# rat_redraw.net
KiCad netlist of a schematic drawn in EAGLE
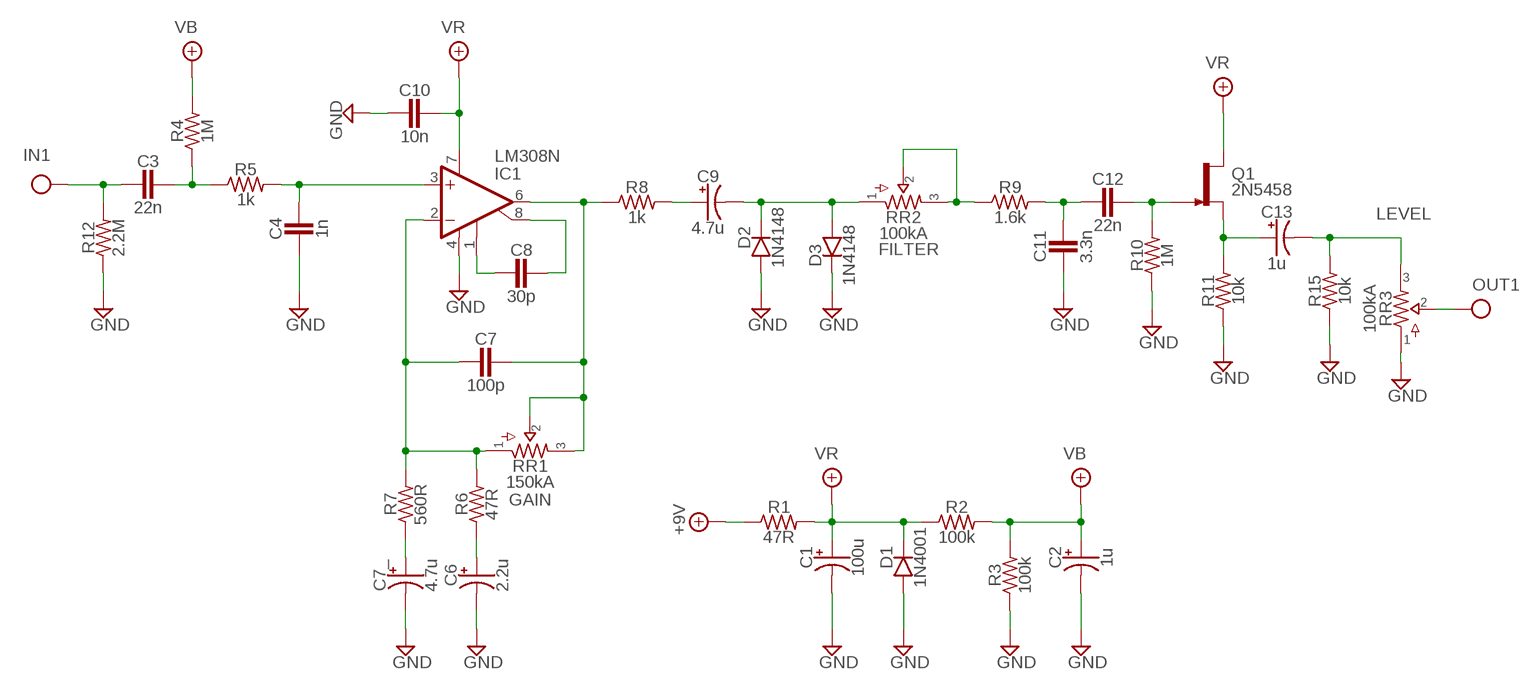
[diagram p0: schematic, sheet 1]

(export (version "E")
  (design (tool "Eeschema 10.0.6"))
  (components
    (comp (ref "C1")
      (value "100u")
      (footprint "eagle-import:040_020")
      (libsource (lib "eagle-import") (part "0400"))
    )
    (comp (ref "C2")
      (value "1u")
      (footprint "eagle-import:040_020")
      (libsource (lib "eagle-import") (part "0400"))
    )
    (comp (ref "C3")
      (value "22n")
      (footprint "eagle-import:BOX_SMALL")
      (libsource (lib "eagle-import") (part "CER/FILMBOX.1"))
    )
    (comp (ref "C4")
      (value "1n")
      (footprint "eagle-import:BOX_SMALL")
      (libsource (lib "eagle-import") (part "CER/FILMBOX.1"))
    )
    (comp (ref "C6")
      (value "2.2u")
      (footprint "eagle-import:050_020")
      (libsource (lib "eagle-import") (part "0500"))
    )
    (comp (ref "C7")
      (value "100p")
      (footprint "eagle-import:050X030_025_2")
      (libsource (lib "eagle-import") (part "CER/FILM2"))
    )
    (comp (ref "C7_")
      (value "4.7u")
      (footprint "eagle-import:050_020")
      (libsource (lib "eagle-import") (part "0500"))
    )
    (comp (ref "C8")
      (value "30p")
      (footprint "eagle-import:050X030_025_2")
      (libsource (lib "eagle-import") (part "CER/FILM2"))
    )
    (comp (ref "C9")
      (value "4.7u")
      (footprint "eagle-import:050_020")
      (libsource (lib "eagle-import") (part "0500"))
    )
    (comp (ref "C10")
      (value "10n")
      (footprint "eagle-import:050X030_025_2")
      (libsource (lib "eagle-import") (part "CER/FILM2"))
    )
    (comp (ref "C11")
      (value "3.3n")
      (footprint "eagle-import:BOX_SMALL")
      (libsource (lib "eagle-import") (part "CER/FILMBOX.1"))
    )
    (comp (ref "C12")
      (value "22n")
      (footprint "eagle-import:BOX_SMALL")
      (libsource (lib "eagle-import") (part "CER/FILMBOX.1"))
    )
    (comp (ref "C13")
      (value "1u")
      (footprint "eagle-import:050_020")
      (libsource (lib "eagle-import") (part "0500"))
    )
    (comp (ref "D1")
      (value "1N4001")
      (footprint "eagle-import:DO35-2")
      (libsource (lib "eagle-import") (part "DO35.2"))
    )
    (comp (ref "D2")
      (value "1N4148")
      (footprint "eagle-import:DO35-2")
      (libsource (lib "eagle-import") (part "DO35.2"))
    )
    (comp (ref "D3")
      (value "1N4148")
      (footprint "eagle-import:DO35-2")
      (libsource (lib "eagle-import") (part "DO35.2"))
    )
    (comp (ref "IC1")
      (value "LM308N")
      (footprint "eagle-import:DIL0")
      (libsource (lib "eagle-import") (part "LM308N"))
    )
    (comp (ref "Q1")
      (value "2N5458")
      (footprint "eagle-import:TO92-")
      (libsource (lib "eagle-import") (part "2N5457"))
    )
    (comp (ref "R1")
      (value "47R")
      (footprint "eagle-import:R0207_3")
      (libsource (lib "eagle-import") (part "R_.3B"))
    )
    (comp (ref "R2")
      (value "100k")
      (footprint "eagle-import:R0207_3")
      (libsource (lib "eagle-import") (part "R_.3B"))
    )
    (comp (ref "R3")
      (value "100k")
      (footprint "eagle-import:R0207_3")
      (libsource (lib "eagle-import") (part "R_.3B"))
    )
    (comp (ref "R4")
      (value "1M")
      (footprint "eagle-import:R0207_3")
      (libsource (lib "eagle-import") (part "R_.3B"))
    )
    (comp (ref "R5")
      (value "1k")
      (footprint "eagle-import:R0207_3")
      (libsource (lib "eagle-import") (part "R_.3B"))
    )
    (comp (ref "R6")
      (value "47R")
      (footprint "eagle-import:R0207_3")
      (libsource (lib "eagle-import") (part "R_.3B"))
    )
    (comp (ref "R7")
      (value "560R")
      (footprint "eagle-import:R0207_3")
      (libsource (lib "eagle-import") (part "R_.3B"))
    )
    (comp (ref "R8")
      (value "1k")
      (footprint "eagle-import:R0207_3")
      (libsource (lib "eagle-import") (part "R_.3B"))
    )
    (comp (ref "R9")
      (value "1.6k")
      (footprint "eagle-import:R0207_3")
      (libsource (lib "eagle-import") (part "R_.3B"))
    )
    (comp (ref "R10")
      (value "1M")
      (footprint "eagle-import:R0207_3")
      (libsource (lib "eagle-import") (part "R_.3B"))
    )
    (comp (ref "R11")
      (value "10k")
      (footprint "eagle-import:R0207_3")
      (libsource (lib "eagle-import") (part "R_.3B"))
    )
    (comp (ref "R12")
      (value "2.2M")
      (footprint "eagle-import:R0207_3")
      (libsource (lib "eagle-import") (part "R_.3B"))
    )
    (comp (ref "R15")
      (value "10k")
      (footprint "eagle-import:R0207_3")
      (libsource (lib "eagle-import") (part "R_.3B"))
    )
    (comp (ref "RR1")
      (value "150kA")
      (footprint "eagle-import:16MM")
      (libsource (lib "eagle-import") (part "POTS16MM"))
    )
    (comp (ref "RR2")
      (value "100kA")
      (footprint "eagle-import:16MM")
      (libsource (lib "eagle-import") (part "POTS16MM"))
    )
    (comp (ref "RR3")
      (value "100kA")
      (footprint "eagle-import:16MM")
      (libsource (lib "eagle-import") (part "POTS16MM"))
    )
  )
  (nets
    (net (code "1") (name "+9V") (class "Default")
      (node (ref "R1") (pin "1") (pinfunction "1_1") (pintype "passive"))
    )
    (net (code "2") (name "GND") (class "Default")
      (node (ref "C1") (pin "-") (pinfunction "-_-") (pintype "passive"))
      (node (ref "C10") (pin "2") (pinfunction "2_2") (pintype "passive"))
      (node (ref "C11") (pin "2") (pinfunction "2_2") (pintype "passive"))
      (node (ref "C2") (pin "-") (pinfunction "-_-") (pintype "passive"))
      (node (ref "C4") (pin "2") (pinfunction "2_2") (pintype "passive"))
      (node (ref "C6") (pin "-") (pinfunction "-_-") (pintype "passive"))
      (node (ref "C7_") (pin "-") (pinfunction "-_-") (pintype "passive"))
      (node (ref "D1") (pin "A") (pinfunction "A_A") (pintype "passive"))
      (node (ref "D2") (pin "A") (pinfunction "A_A") (pintype "passive"))
      (node (ref "D3") (pin "C") (pinfunction "C_C") (pintype "passive"))
      (node (ref "IC1") (pin "4") (pinfunction "V-_4") (pintype "power_in"))
      (node (ref "R10") (pin "1") (pinfunction "1_1") (pintype "passive"))
      (node (ref "R11") (pin "1") (pinfunction "1_1") (pintype "passive"))
      (node (ref "R12") (pin "1") (pinfunction "1_1") (pintype "passive"))
      (node (ref "R15") (pin "1") (pinfunction "1_1") (pintype "passive"))
      (node (ref "R3") (pin "1") (pinfunction "1_1") (pintype "passive"))
      (node (ref "RR3") (pin "1") (pinfunction "1_1") (pintype "passive"))
    )
    (net (code "3") (name "IN") (class "Default")
      (node (ref "C3") (pin "2") (pinfunction "2_2") (pintype "passive"))
      (node (ref "R12") (pin "2") (pinfunction "2_2") (pintype "passive"))
    )
    (net (code "4") (name "Net-(C3-Pad1)") (class "Default")
      (node (ref "C3") (pin "1") (pinfunction "1_1") (pintype "passive"))
      (node (ref "R4") (pin "1") (pinfunction "1_1") (pintype "passive"))
      (node (ref "R5") (pin "1") (pinfunction "1_1") (pintype "passive"))
    )
    (net (code "5") (name "Net-(C6-Pad+)") (class "Default")
      (node (ref "C6") (pin "+") (pinfunction "+_+") (pintype "passive"))
      (node (ref "R6") (pin "1") (pinfunction "1_1") (pintype "passive"))
    )
    (net (code "6") (name "Net-(C7_-Pad+)") (class "Default")
      (node (ref "C7_") (pin "+") (pinfunction "+_+") (pintype "passive"))
      (node (ref "R7") (pin "1") (pinfunction "1_1") (pintype "passive"))
    )
    (net (code "7") (name "Net-(C9-Pad+)") (class "Default")
      (node (ref "C9") (pin "+") (pinfunction "+_+") (pintype "passive"))
      (node (ref "R8") (pin "2") (pinfunction "2_2") (pintype "passive"))
    )
    (net (code "8") (name "Net-(C9-Pad-)") (class "Default")
      (node (ref "C9") (pin "-") (pinfunction "-_-") (pintype "passive"))
      (node (ref "D2") (pin "C") (pinfunction "C_C") (pintype "passive"))
      (node (ref "D3") (pin "A") (pinfunction "A_A") (pintype "passive"))
      (node (ref "RR2") (pin "1") (pinfunction "1_1") (pintype "passive"))
    )
    (net (code "9") (name "Net-(C11-Pad1)") (class "Default")
      (node (ref "C11") (pin "1") (pinfunction "1_1") (pintype "passive"))
      (node (ref "C12") (pin "2") (pinfunction "2_2") (pintype "passive"))
      (node (ref "R9") (pin "2") (pinfunction "2_2") (pintype "passive"))
    )
    (net (code "10") (name "Net-(C13-Pad-)") (class "Default")
      (node (ref "C13") (pin "-") (pinfunction "-_-") (pintype "passive"))
      (node (ref "R15") (pin "2") (pinfunction "2_2") (pintype "passive"))
      (node (ref "RR3") (pin "3") (pinfunction "3_3") (pintype "passive"))
    )
    (net (code "11") (name "Net-(IC1-+IN)") (class "Default")
      (node (ref "C4") (pin "1") (pinfunction "1_1") (pintype "passive"))
      (node (ref "IC1") (pin "3") (pinfunction "+IN_3") (pintype "input"))
      (node (ref "R5") (pin "2") (pinfunction "2_2") (pintype "passive"))
    )
    (net (code "12") (name "Net-(IC1--IN)") (class "Default")
      (node (ref "C7") (pin "2") (pinfunction "2_2") (pintype "passive"))
      (node (ref "IC1") (pin "2") (pinfunction "-IN_2") (pintype "input"))
      (node (ref "R6") (pin "2") (pinfunction "2_2") (pintype "passive"))
      (node (ref "R7") (pin "2") (pinfunction "2_2") (pintype "passive"))
      (node (ref "RR1") (pin "1") (pinfunction "1_1") (pintype "passive"))
    )
    (net (code "13") (name "Net-(IC1-CMP1)") (class "Default")
      (node (ref "C8") (pin "2") (pinfunction "2_2") (pintype "passive"))
      (node (ref "IC1") (pin "1") (pinfunction "CMP1_1") (pintype "passive"))
    )
    (net (code "14") (name "Net-(IC1-CMP2)") (class "Default")
      (node (ref "C8") (pin "1") (pinfunction "1_1") (pintype "passive"))
      (node (ref "IC1") (pin "8") (pinfunction "CMP2_8") (pintype "passive"))
    )
    (net (code "15") (name "Net-(IC1-OUT)") (class "Default")
      (node (ref "C7") (pin "1") (pinfunction "1_1") (pintype "passive"))
      (node (ref "IC1") (pin "6") (pinfunction "OUT_6") (pintype "output"))
      (node (ref "R8") (pin "1") (pinfunction "1_1") (pintype "passive"))
      (node (ref "RR1") (pin "2") (pinfunction "2_2") (pintype "passive"))
      (node (ref "RR1") (pin "3") (pinfunction "3_3") (pintype "passive"))
    )
    (net (code "16") (name "Net-(Q1-G)") (class "Default")
      (node (ref "C12") (pin "1") (pinfunction "1_1") (pintype "passive"))
      (node (ref "Q1") (pin "1") (pinfunction "G_1") (pintype "passive"))
      (node (ref "R10") (pin "2") (pinfunction "2_2") (pintype "passive"))
    )
    (net (code "17") (name "Net-(Q1-S)") (class "Default")
      (node (ref "C13") (pin "+") (pinfunction "+_+") (pintype "passive"))
      (node (ref "Q1") (pin "2") (pinfunction "S_2") (pintype "passive"))
      (node (ref "R11") (pin "2") (pinfunction "2_2") (pintype "passive"))
    )
    (net (code "18") (name "Net-(R9-Pad1)") (class "Default")
      (node (ref "R9") (pin "1") (pinfunction "1_1") (pintype "passive"))
      (node (ref "RR2") (pin "2") (pinfunction "2_2") (pintype "passive"))
      (node (ref "RR2") (pin "3") (pinfunction "3_3") (pintype "passive"))
    )
    (net (code "19") (name "OUT") (class "Default")
      (node (ref "RR3") (pin "2") (pinfunction "2_2") (pintype "passive"))
    )
    (net (code "20") (name "VB") (class "Default")
      (node (ref "C2") (pin "+") (pinfunction "+_+") (pintype "passive"))
      (node (ref "R2") (pin "2") (pinfunction "2_2") (pintype "passive"))
      (node (ref "R3") (pin "2") (pinfunction "2_2") (pintype "passive"))
      (node (ref "R4") (pin "2") (pinfunction "2_2") (pintype "passive"))
    )
    (net (code "21") (name "VR") (class "Default")
      (node (ref "C1") (pin "+") (pinfunction "+_+") (pintype "passive"))
      (node (ref "C10") (pin "1") (pinfunction "1_1") (pintype "passive"))
      (node (ref "D1") (pin "C") (pinfunction "C_C") (pintype "passive"))
      (node (ref "IC1") (pin "7") (pinfunction "V+_7") (pintype "power_in"))
      (node (ref "Q1") (pin "3") (pinfunction "D_3") (pintype "passive"))
      (node (ref "R1") (pin "2") (pinfunction "2_2") (pintype "passive"))
      (node (ref "R2") (pin "1") (pinfunction "1_1") (pintype "passive"))
    )
  )
)
